# System.net
KiCad netlist of a schematic drawn in Altium Designer
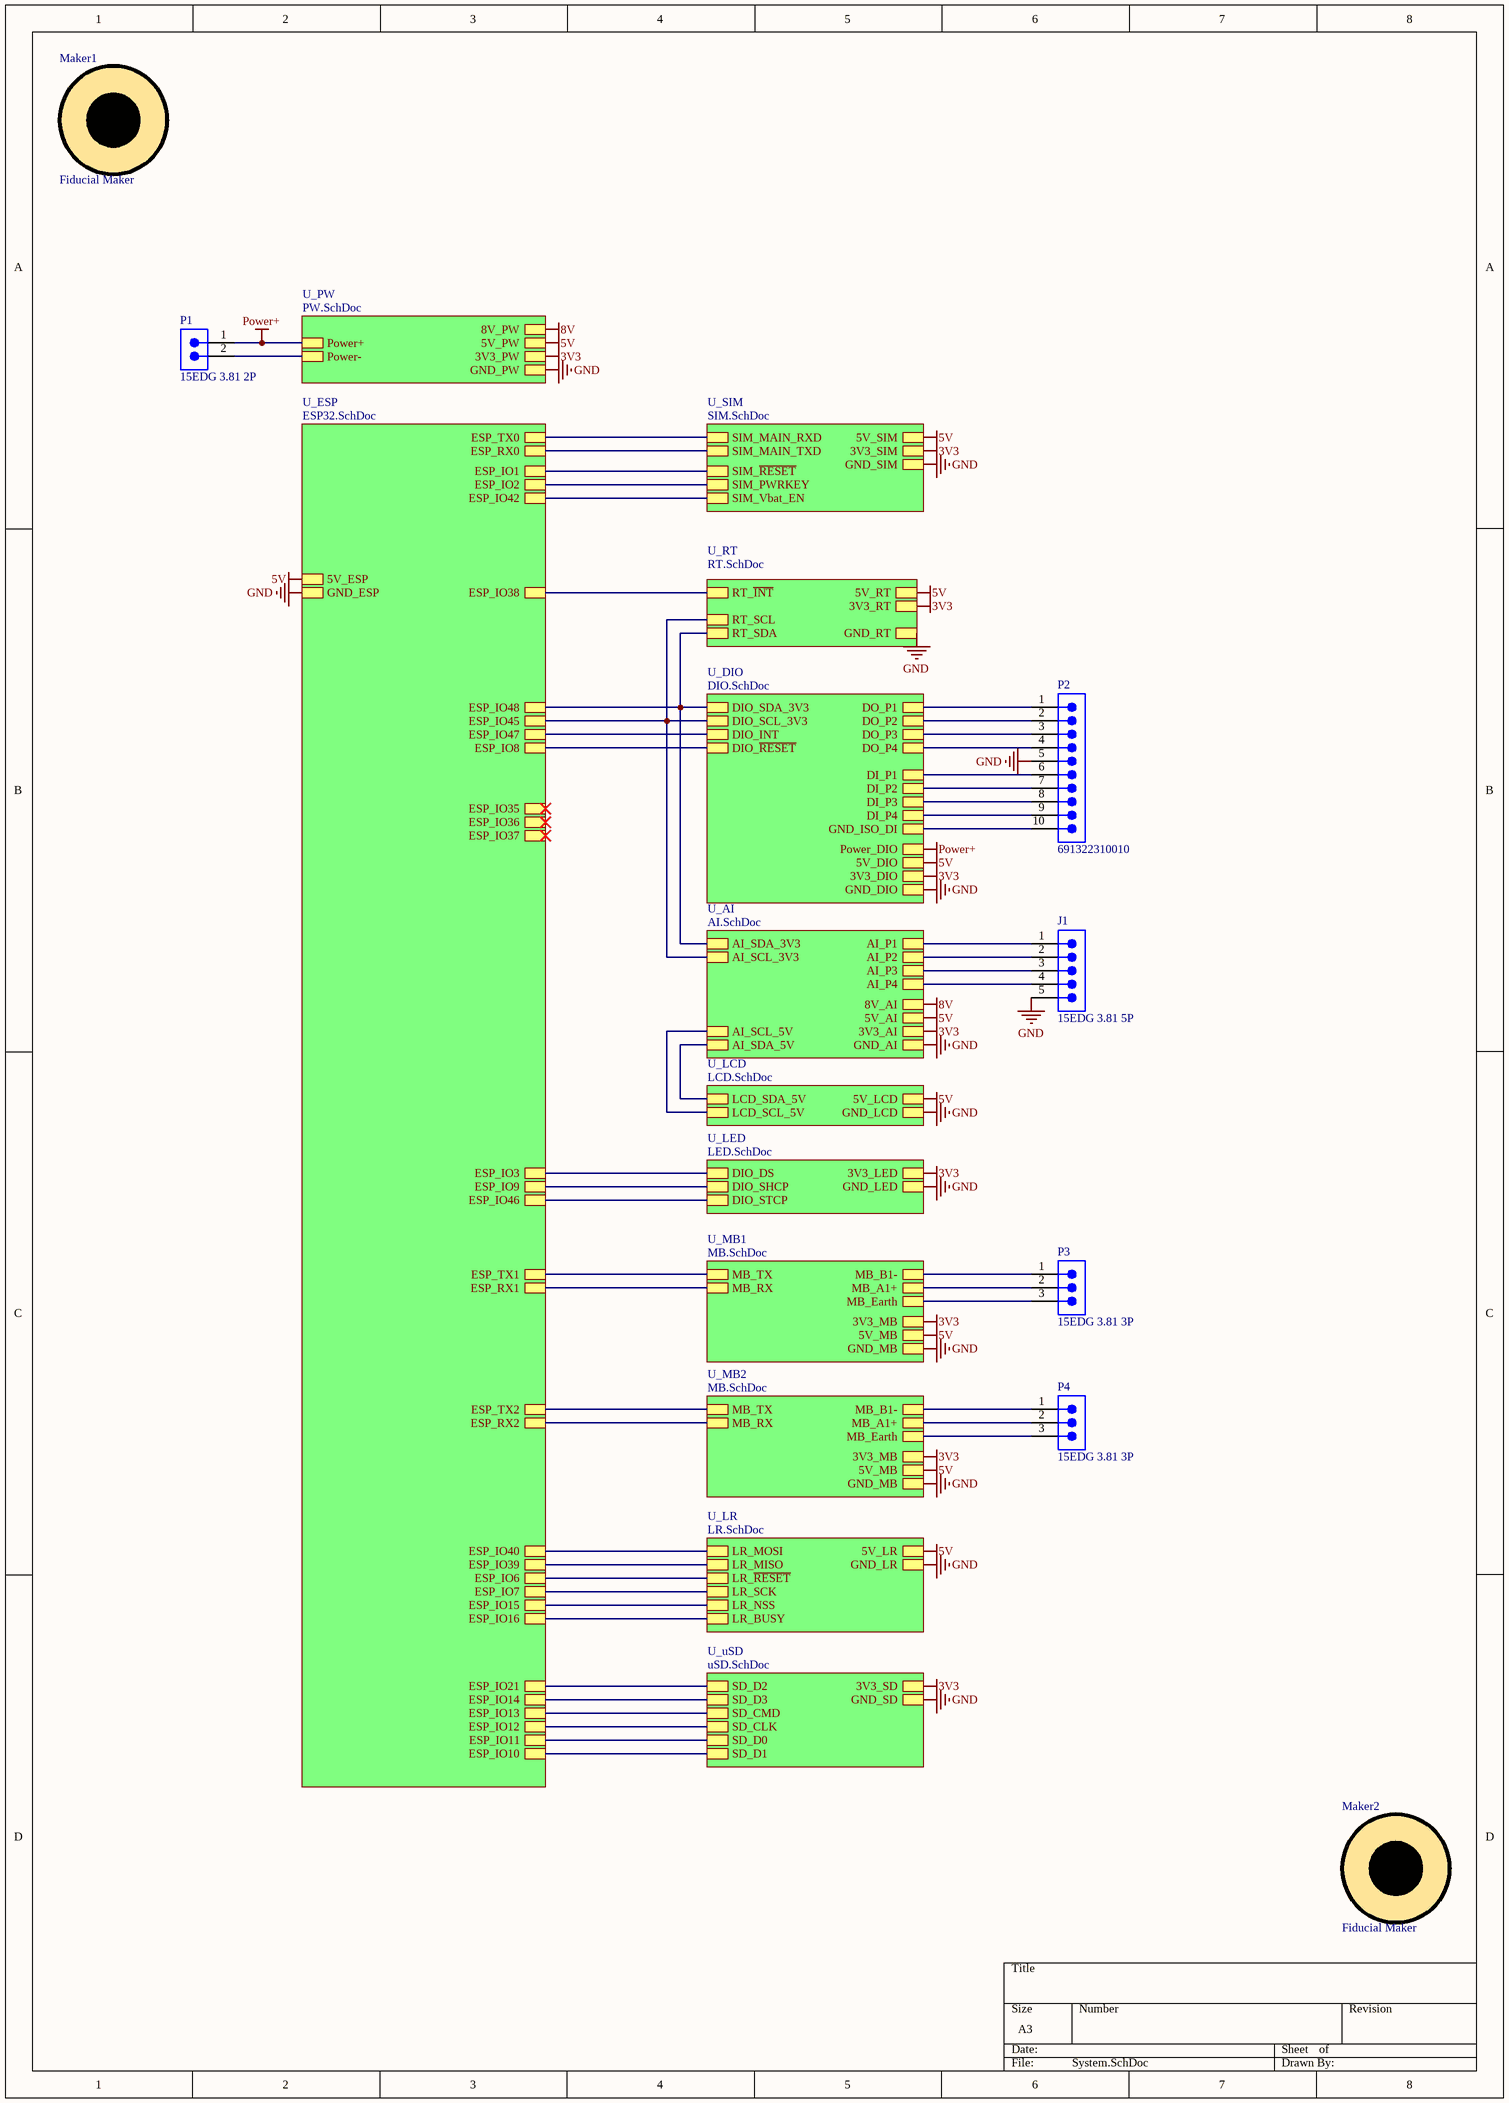
[diagram p0: System.SchDoc]

(export (version "E")
  (design (tool "Eeschema 10.0.6"))
  (components
    (comp (ref "J1")
      (value "15EDG 3.81 5P")
      (footprint "691322310005")
      (description "Cầu Đấu Terminal Cong 15EDG 3.81mm 5P")
      (fields (field (name "VOLTAGE") "300V"))
      (libsource (lib "Altium Content Vault") (part "TBL - 1R - 05P - Male"))
    )
    (comp (ref "Maker1")
      (value "Fiducial Maker")
      (footprint "Fiducial Maker")
      (libsource (lib "atlab_altium_lib") (part "Fiducial Maker"))
    )
    (comp (ref "Maker2")
      (value "Fiducial Maker")
      (footprint "Fiducial Maker")
      (libsource (lib "atlab_altium_lib") (part "Fiducial Maker"))
    )
    (comp (ref "P1")
      (value "15EDG 3.81 2P")
      (footprint "691322310002")
      (fields (field (name "VOLTAGE") "300V"))
      (libsource (lib "Altium Content Vault") (part "TBL - 1R - 02P - Male"))
    )
    (comp (ref "P2")
      (value "691322310010")
      (footprint "691322310010")
      (libsource (lib "Altium Content Vault") (part "TBL - 1R - 10P - Male"))
    )
    (comp (ref "P3")
      (value "15EDG 3.81 3P")
      (footprint "691322310003")
      (fields (field (name "VOLTAGE") "300V"))
      (libsource (lib "Altium Content Vault") (part "TBL - 1R - 03P - Male"))
    )
    (comp (ref "P4")
      (value "15EDG 3.81 3P")
      (footprint "691322310003")
      (fields (field (name "VOLTAGE") "300V"))
      (libsource (lib "Altium Content Vault") (part "TBL - 1R - 03P - Male"))
    )
  )
  (nets
    (net (code "1") (name "/AI_P1") (class "Default")
      (node (ref "J1") (pin "1") (pinfunction "1_1") (pintype "passive"))
    )
    (net (code "2") (name "/AI_P2") (class "Default")
      (node (ref "J1") (pin "2") (pinfunction "2_2") (pintype "passive"))
    )
    (net (code "3") (name "/AI_P3") (class "Default")
      (node (ref "J1") (pin "3") (pinfunction "3_3") (pintype "passive"))
    )
    (net (code "4") (name "/AI_P4") (class "Default")
      (node (ref "J1") (pin "4") (pinfunction "4_4") (pintype "passive"))
    )
    (net (code "14") (name "/DI_P1") (class "Default")
      (node (ref "P2") (pin "6") (pinfunction "6_6") (pintype "passive"))
    )
    (net (code "15") (name "/DI_P2") (class "Default")
      (node (ref "P2") (pin "7") (pinfunction "7_7") (pintype "passive"))
    )
    (net (code "16") (name "/DI_P3") (class "Default")
      (node (ref "P2") (pin "8") (pinfunction "8_8") (pintype "passive"))
    )
    (net (code "17") (name "/DI_P4") (class "Default")
      (node (ref "P2") (pin "9") (pinfunction "9_9") (pintype "passive"))
    )
    (net (code "18") (name "/DO_P1") (class "Default")
      (node (ref "P2") (pin "1") (pinfunction "1_1") (pintype "passive"))
    )
    (net (code "19") (name "/DO_P2") (class "Default")
      (node (ref "P2") (pin "2") (pinfunction "2_2") (pintype "passive"))
    )
    (net (code "20") (name "/DO_P3") (class "Default")
      (node (ref "P2") (pin "3") (pinfunction "3_3") (pintype "passive"))
    )
    (net (code "21") (name "/DO_P4") (class "Default")
      (node (ref "P2") (pin "4") (pinfunction "4_4") (pintype "passive"))
    )
    (net (code "47") (name "/GND_ISO_DI") (class "Default")
      (node (ref "P2") (pin "10") (pinfunction "10_10") (pintype "passive"))
    )
    (net (code "48") (name "/MB_A1+") (class "Default")
      (node (ref "P3") (pin "2") (pinfunction "2_2") (pintype "passive"))
    )
    (net (code "49") (name "/MB_A1+_1") (class "Default")
      (node (ref "P4") (pin "2") (pinfunction "2_2") (pintype "passive"))
    )
    (net (code "50") (name "/MB_B1-") (class "Default")
      (node (ref "P3") (pin "1") (pinfunction "1_1") (pintype "passive"))
    )
    (net (code "51") (name "/MB_B1-_1") (class "Default")
      (node (ref "P4") (pin "1") (pinfunction "1_1") (pintype "passive"))
    )
    (net (code "52") (name "/MB_Earth") (class "Default")
      (node (ref "P3") (pin "3") (pinfunction "3_3") (pintype "passive"))
    )
    (net (code "53") (name "/MB_Earth_1") (class "Default")
      (node (ref "P4") (pin "3") (pinfunction "3_3") (pintype "passive"))
    )
    (net (code "54") (name "/Power-") (class "Default")
      (node (ref "P1") (pin "2") (pinfunction "2_2") (pintype "passive"))
    )
    (net (code "58") (name "GND") (class "Default")
      (node (ref "J1") (pin "5") (pinfunction "5_5") (pintype "passive"))
      (node (ref "P2") (pin "5") (pinfunction "5_5") (pintype "passive"))
    )
    (net (code "59") (name "Power+") (class "Default")
      (node (ref "P1") (pin "1") (pinfunction "1_1") (pintype "passive"))
    )
  )
)
